# single_breakoutmicrosh.net
KiCad netlist of a schematic drawn in EAGLE
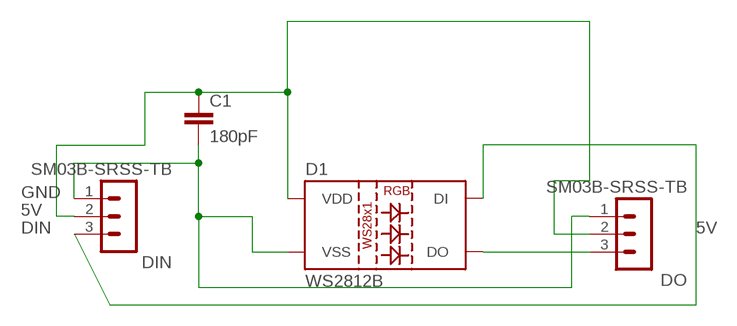
[diagram p0: schematic, sheet 1]

(export (version "E")
  (design (tool "Eeschema 10.0.6"))
  (components
    (comp (ref "C1")
      (value "180pF")
      (footprint "eagle-import:0603")
      (libsource (lib "eagle-import") (part "180PF-0603-50V-5%"))
    )
    (comp (ref "D1")
      (value "WS2812B")
      (footprint "eagle-import:WS2812B")
      (libsource (lib "eagle-import") (part "WS2812B"))
    )
    (comp (ref "DIN")
      (value "SM03B-SRSS-TB")
      (footprint "eagle-import:SM03B-SRSS-TB")
      (libsource (lib "eagle-import") (part "SM03B-SRSS-TB"))
    )
    (comp (ref "DO")
      (value "SM03B-SRSS-TB")
      (footprint "eagle-import:SM03B-SRSS-TB")
      (libsource (lib "eagle-import") (part "SM03B-SRSS-TB"))
    )
  )
  (nets
    (net (code "1") (name "/5V") (class "Default")
      (node (ref "C1") (pin "1") (pinfunction "1_1") (pintype "passive"))
      (node (ref "D1") (pin "1") (pinfunction "VDD_1") (pintype "bidirectional"))
      (node (ref "DIN") (pin "2") (pinfunction "2_2") (pintype "passive"))
      (node (ref "DO") (pin "2") (pinfunction "2_2") (pintype "passive"))
    )
    (net (code "2") (name "/DIN") (class "Default")
      (node (ref "D1") (pin "4") (pinfunction "DI_4") (pintype "bidirectional"))
      (node (ref "DIN") (pin "3") (pinfunction "3_3") (pintype "passive"))
    )
    (net (code "3") (name "/GND") (class "Default")
      (node (ref "C1") (pin "2") (pinfunction "2_2") (pintype "passive"))
      (node (ref "D1") (pin "3") (pinfunction "VSS_3") (pintype "bidirectional"))
      (node (ref "DIN") (pin "1") (pinfunction "1_1") (pintype "passive"))
      (node (ref "DO") (pin "1") (pinfunction "1_1") (pintype "passive"))
    )
    (net (code "4") (name "Net-(D1-DO)") (class "Default")
      (node (ref "D1") (pin "2") (pinfunction "DO_2") (pintype "bidirectional"))
      (node (ref "DO") (pin "3") (pinfunction "3_3") (pintype "passive"))
    )
  )
)
